# YOTSUBA_AP_EM_ver_4_0.net
KiCad netlist of a schematic drawn in EAGLE
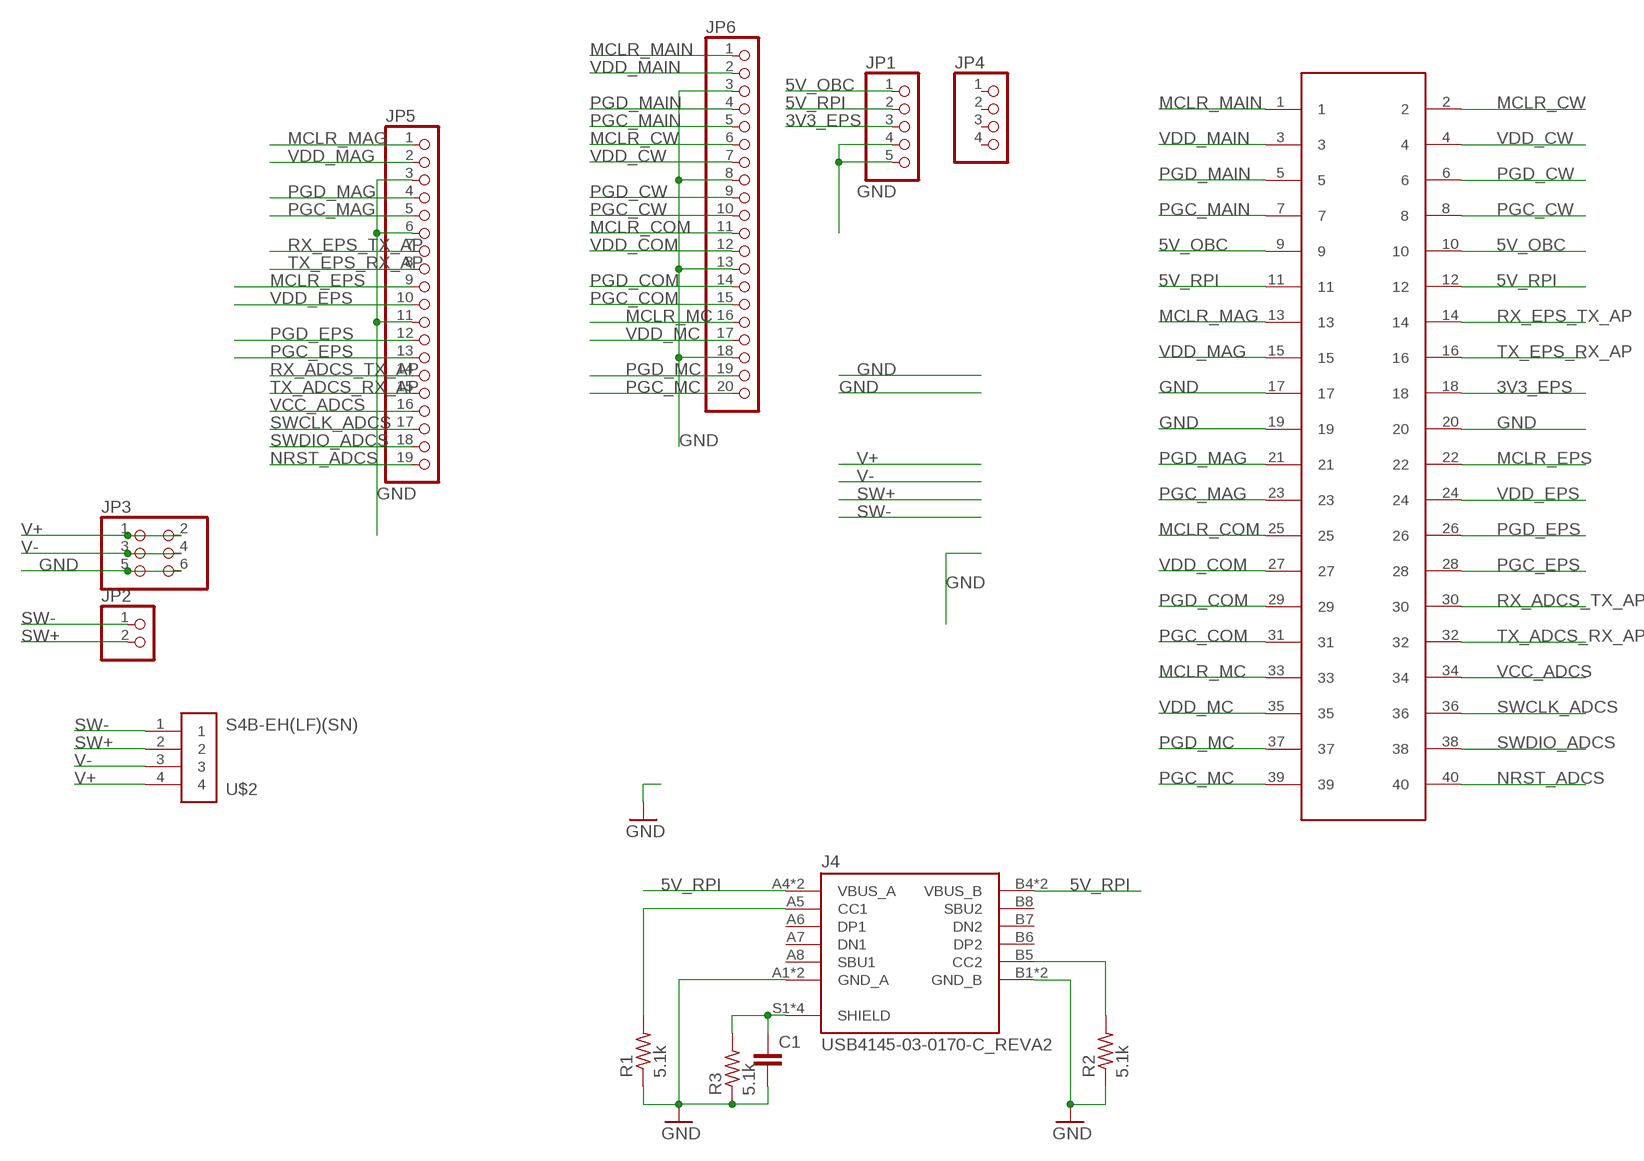
[diagram p0: schematic, sheet 1]

(export (version "E")
  (design (tool "Eeschema 10.0.6"))
  (components
    (comp (ref "C1")
      (value "C-EUC2012")
      (footprint "eagle-import:C2012")
      (libsource (lib "eagle-import") (part "C-EUC2012"))
    )
    (comp (ref "J4")
      (value "USB4145-03-0170-C_REVA2")
      (footprint "eagle-import:GCT_USB4145-03-0170-C_REVA2")
      (fields (field (name "MF") "Global Connector Technology") (field (name "MP") "USB4145-03-0170-C"))
      (libsource (lib "eagle-import") (part "USB4145-03-0170-C_REVA2"))
    )
    (comp (ref "JP1")
      (value "PINHD-1X5")
      (footprint "eagle-import:1X05")
      (libsource (lib "eagle-import") (part "PINHD-1X5"))
    )
    (comp (ref "JP2")
      (value "PINHD-1X2")
      (footprint "eagle-import:1X02")
      (libsource (lib "eagle-import") (part "PINHD-1X2"))
    )
    (comp (ref "JP3")
      (value "PINHD-2X3")
      (footprint "eagle-import:2X03")
      (libsource (lib "eagle-import") (part "PINHD-2X3"))
    )
    (comp (ref "JP4")
      (value "PINHD-1X4")
      (footprint "eagle-import:1X04")
      (libsource (lib "eagle-import") (part "PINHD-1X4"))
    )
    (comp (ref "JP5")
      (value "PINHD-1X19")
      (footprint "eagle-import:1X19")
      (libsource (lib "eagle-import") (part "PINHD-1X19"))
    )
    (comp (ref "JP6")
      (value "PINHD-1X20")
      (footprint "eagle-import:1X20")
      (libsource (lib "eagle-import") (part "PINHD-1X20"))
    )
    (comp (ref "R1")
      (value "5.1k")
      (footprint "eagle-import:R0805")
      (libsource (lib "eagle-import") (part "R-US_R0805"))
    )
    (comp (ref "R2")
      (value "5.1k")
      (footprint "eagle-import:R0805")
      (libsource (lib "eagle-import") (part "R-US_R0805"))
    )
    (comp (ref "R3")
      (value "5.1k")
      (footprint "eagle-import:R0805")
      (libsource (lib "eagle-import") (part "R-US_R0805"))
    )
    (comp (ref "U$1")
      (value "M50-3902042")
      (footprint "eagle-import:M50-3902042")
      (libsource (lib "eagle-import") (part "M50-3902042"))
    )
    (comp (ref "U$2")
      (value "S4B-EH(LF)(SN)")
      (footprint "eagle-import:JST_S4B-EH(LF)(SN)")
      (fields (field (name "MF") "JST Sales"))
      (libsource (lib "eagle-import") (part "S4B-EH(LF)(SN)"))
    )
  )
  (nets
    (net (code "1") (name "/3V3_EPS") (class "Default")
      (node (ref "JP1") (pin "3") (pinfunction "3_3") (pintype "passive"))
      (node (ref "U$1") (pin "18") (pinfunction "18_18") (pintype "bidirectional"))
    )
    (net (code "2") (name "/5V_OBC") (class "Default")
      (node (ref "JP1") (pin "1") (pinfunction "1_1") (pintype "passive"))
      (node (ref "U$1") (pin "10") (pinfunction "10_10") (pintype "bidirectional"))
      (node (ref "U$1") (pin "9") (pinfunction "9_9") (pintype "bidirectional"))
    )
    (net (code "3") (name "/5V_RPI") (class "Default")
      (node (ref "J4") (pin "A4") (pinfunction "VBUS_A_A4") (pintype "power_in"))
      (node (ref "J4") (pin "A9") (pinfunction "VBUS_A_A9") (pintype "power_in"))
      (node (ref "J4") (pin "B4") (pinfunction "VBUS_B_B4") (pintype "power_in"))
      (node (ref "J4") (pin "B9") (pinfunction "VBUS_B_B9") (pintype "power_in"))
      (node (ref "JP1") (pin "2") (pinfunction "2_2") (pintype "passive"))
      (node (ref "U$1") (pin "11") (pinfunction "11_11") (pintype "bidirectional"))
      (node (ref "U$1") (pin "12") (pinfunction "12_12") (pintype "bidirectional"))
    )
    (net (code "4") (name "/MCLR_COM") (class "Default")
      (node (ref "JP6") (pin "11") (pinfunction "11_11") (pintype "passive"))
      (node (ref "U$1") (pin "25") (pinfunction "25_25") (pintype "bidirectional"))
    )
    (net (code "5") (name "/MCLR_CW") (class "Default")
      (node (ref "JP6") (pin "6") (pinfunction "6_6") (pintype "passive"))
      (node (ref "U$1") (pin "2") (pinfunction "2_2") (pintype "bidirectional"))
    )
    (net (code "6") (name "/MCLR_EPS") (class "Default")
      (node (ref "JP5") (pin "9") (pinfunction "9_9") (pintype "passive"))
      (node (ref "U$1") (pin "22") (pinfunction "22_22") (pintype "bidirectional"))
    )
    (net (code "7") (name "/MCLR_MAG") (class "Default")
      (node (ref "JP5") (pin "1") (pinfunction "1_1") (pintype "passive"))
      (node (ref "U$1") (pin "13") (pinfunction "13_13") (pintype "bidirectional"))
    )
    (net (code "8") (name "/MCLR_MAIN") (class "Default")
      (node (ref "JP6") (pin "1") (pinfunction "1_1") (pintype "passive"))
      (node (ref "U$1") (pin "1") (pinfunction "1_1") (pintype "bidirectional"))
    )
    (net (code "9") (name "/MCLR_MC") (class "Default")
      (node (ref "JP6") (pin "16") (pinfunction "16_16") (pintype "passive"))
      (node (ref "U$1") (pin "33") (pinfunction "33_33") (pintype "bidirectional"))
    )
    (net (code "10") (name "/NRST_ADCS") (class "Default")
      (node (ref "JP5") (pin "19") (pinfunction "19_19") (pintype "passive"))
      (node (ref "U$1") (pin "40") (pinfunction "40_40") (pintype "bidirectional"))
    )
    (net (code "11") (name "/PGC_COM") (class "Default")
      (node (ref "JP6") (pin "15") (pinfunction "15_15") (pintype "passive"))
      (node (ref "U$1") (pin "31") (pinfunction "31_31") (pintype "bidirectional"))
    )
    (net (code "12") (name "/PGC_CW") (class "Default")
      (node (ref "JP6") (pin "10") (pinfunction "10_10") (pintype "passive"))
      (node (ref "U$1") (pin "8") (pinfunction "8_8") (pintype "bidirectional"))
    )
    (net (code "13") (name "/PGC_EPS") (class "Default")
      (node (ref "JP5") (pin "13") (pinfunction "13_13") (pintype "passive"))
      (node (ref "U$1") (pin "28") (pinfunction "28_28") (pintype "bidirectional"))
    )
    (net (code "14") (name "/PGC_MAG") (class "Default")
      (node (ref "JP5") (pin "5") (pinfunction "5_5") (pintype "passive"))
      (node (ref "U$1") (pin "23") (pinfunction "23_23") (pintype "bidirectional"))
    )
    (net (code "15") (name "/PGC_MAIN") (class "Default")
      (node (ref "JP6") (pin "5") (pinfunction "5_5") (pintype "passive"))
      (node (ref "U$1") (pin "7") (pinfunction "7_7") (pintype "bidirectional"))
    )
    (net (code "16") (name "/PGC_MC") (class "Default")
      (node (ref "JP6") (pin "20") (pinfunction "20_20") (pintype "passive"))
      (node (ref "U$1") (pin "39") (pinfunction "39_39") (pintype "bidirectional"))
    )
    (net (code "17") (name "/PGD_COM") (class "Default")
      (node (ref "JP6") (pin "14") (pinfunction "14_14") (pintype "passive"))
      (node (ref "U$1") (pin "29") (pinfunction "29_29") (pintype "bidirectional"))
    )
    (net (code "18") (name "/PGD_CW") (class "Default")
      (node (ref "JP6") (pin "9") (pinfunction "9_9") (pintype "passive"))
      (node (ref "U$1") (pin "6") (pinfunction "6_6") (pintype "bidirectional"))
    )
    (net (code "19") (name "/PGD_EPS") (class "Default")
      (node (ref "JP5") (pin "12") (pinfunction "12_12") (pintype "passive"))
      (node (ref "U$1") (pin "26") (pinfunction "26_26") (pintype "bidirectional"))
    )
    (net (code "20") (name "/PGD_MAG") (class "Default")
      (node (ref "JP5") (pin "4") (pinfunction "4_4") (pintype "passive"))
      (node (ref "U$1") (pin "21") (pinfunction "21_21") (pintype "bidirectional"))
    )
    (net (code "21") (name "/PGD_MAIN") (class "Default")
      (node (ref "JP6") (pin "4") (pinfunction "4_4") (pintype "passive"))
      (node (ref "U$1") (pin "5") (pinfunction "5_5") (pintype "bidirectional"))
    )
    (net (code "22") (name "/PGD_MC") (class "Default")
      (node (ref "JP6") (pin "19") (pinfunction "19_19") (pintype "passive"))
      (node (ref "U$1") (pin "37") (pinfunction "37_37") (pintype "bidirectional"))
    )
    (net (code "23") (name "/RX_ADCS_TX_AP") (class "Default")
      (node (ref "JP5") (pin "14") (pinfunction "14_14") (pintype "passive"))
      (node (ref "U$1") (pin "30") (pinfunction "30_30") (pintype "bidirectional"))
    )
    (net (code "24") (name "/RX_EPS_TX_AP") (class "Default")
      (node (ref "JP5") (pin "7") (pinfunction "7_7") (pintype "passive"))
      (node (ref "U$1") (pin "14") (pinfunction "14_14") (pintype "bidirectional"))
    )
    (net (code "25") (name "/SW+") (class "Default")
      (node (ref "JP2") (pin "2") (pinfunction "2_2") (pintype "passive"))
      (node (ref "U$2") (pin "2") (pinfunction "2_2") (pintype "passive"))
    )
    (net (code "26") (name "/SW-") (class "Default")
      (node (ref "JP2") (pin "1") (pinfunction "1_1") (pintype "passive"))
      (node (ref "U$2") (pin "1") (pinfunction "1_1") (pintype "passive"))
    )
    (net (code "27") (name "/SWCLK_ADCS") (class "Default")
      (node (ref "JP5") (pin "17") (pinfunction "17_17") (pintype "passive"))
      (node (ref "U$1") (pin "36") (pinfunction "36_36") (pintype "bidirectional"))
    )
    (net (code "28") (name "/SWDIO_ADCS") (class "Default")
      (node (ref "JP5") (pin "18") (pinfunction "18_18") (pintype "passive"))
      (node (ref "U$1") (pin "38") (pinfunction "38_38") (pintype "bidirectional"))
    )
    (net (code "29") (name "/TX_ADCS_RX_AP") (class "Default")
      (node (ref "JP5") (pin "15") (pinfunction "15_15") (pintype "passive"))
      (node (ref "U$1") (pin "32") (pinfunction "32_32") (pintype "bidirectional"))
    )
    (net (code "30") (name "/TX_EPS_RX_AP") (class "Default")
      (node (ref "JP5") (pin "8") (pinfunction "8_8") (pintype "passive"))
      (node (ref "U$1") (pin "16") (pinfunction "16_16") (pintype "bidirectional"))
    )
    (net (code "31") (name "/V+") (class "Default")
      (node (ref "JP3") (pin "1") (pinfunction "1_1") (pintype "passive"))
      (node (ref "JP3") (pin "2") (pinfunction "2_2") (pintype "passive"))
      (node (ref "U$2") (pin "4") (pinfunction "4_4") (pintype "passive"))
    )
    (net (code "32") (name "/V-") (class "Default")
      (node (ref "JP3") (pin "3") (pinfunction "3_3") (pintype "passive"))
      (node (ref "JP3") (pin "4") (pinfunction "4_4") (pintype "passive"))
      (node (ref "U$2") (pin "3") (pinfunction "3_3") (pintype "passive"))
    )
    (net (code "33") (name "/VCC_ADCS") (class "Default")
      (node (ref "JP5") (pin "16") (pinfunction "16_16") (pintype "passive"))
      (node (ref "U$1") (pin "34") (pinfunction "34_34") (pintype "bidirectional"))
    )
    (net (code "34") (name "/VDD_COM") (class "Default")
      (node (ref "JP6") (pin "12") (pinfunction "12_12") (pintype "passive"))
      (node (ref "U$1") (pin "27") (pinfunction "27_27") (pintype "bidirectional"))
    )
    (net (code "35") (name "/VDD_CW") (class "Default")
      (node (ref "JP6") (pin "7") (pinfunction "7_7") (pintype "passive"))
      (node (ref "U$1") (pin "4") (pinfunction "4_4") (pintype "bidirectional"))
    )
    (net (code "36") (name "/VDD_EPS") (class "Default")
      (node (ref "JP5") (pin "10") (pinfunction "10_10") (pintype "passive"))
      (node (ref "U$1") (pin "24") (pinfunction "24_24") (pintype "bidirectional"))
    )
    (net (code "37") (name "/VDD_MAG") (class "Default")
      (node (ref "JP5") (pin "2") (pinfunction "2_2") (pintype "passive"))
      (node (ref "U$1") (pin "15") (pinfunction "15_15") (pintype "bidirectional"))
    )
    (net (code "38") (name "/VDD_MAIN") (class "Default")
      (node (ref "JP6") (pin "2") (pinfunction "2_2") (pintype "passive"))
      (node (ref "U$1") (pin "3") (pinfunction "3_3") (pintype "bidirectional"))
    )
    (net (code "39") (name "/VDD_MC") (class "Default")
      (node (ref "JP6") (pin "17") (pinfunction "17_17") (pintype "passive"))
      (node (ref "U$1") (pin "35") (pinfunction "35_35") (pintype "bidirectional"))
    )
    (net (code "40") (name "GND") (class "Default")
      (node (ref "C1") (pin "2") (pinfunction "2_2") (pintype "passive"))
      (node (ref "J4") (pin "A1") (pinfunction "GND_A_A1") (pintype "power_in"))
      (node (ref "J4") (pin "A12") (pinfunction "GND_A_A12") (pintype "power_in"))
      (node (ref "J4") (pin "B1") (pinfunction "GND_B_B1") (pintype "power_in"))
      (node (ref "J4") (pin "B12") (pinfunction "GND_B_B12") (pintype "power_in"))
      (node (ref "JP1") (pin "4") (pinfunction "4_4") (pintype "passive"))
      (node (ref "JP1") (pin "5") (pinfunction "5_5") (pintype "passive"))
      (node (ref "JP3") (pin "5") (pinfunction "5_5") (pintype "passive"))
      (node (ref "JP3") (pin "6") (pinfunction "6_6") (pintype "passive"))
      (node (ref "JP5") (pin "11") (pinfunction "11_11") (pintype "passive"))
      (node (ref "JP5") (pin "3") (pinfunction "3_3") (pintype "passive"))
      (node (ref "JP5") (pin "6") (pinfunction "6_6") (pintype "passive"))
      (node (ref "JP6") (pin "13") (pinfunction "13_13") (pintype "passive"))
      (node (ref "JP6") (pin "18") (pinfunction "18_18") (pintype "passive"))
      (node (ref "JP6") (pin "3") (pinfunction "3_3") (pintype "passive"))
      (node (ref "JP6") (pin "8") (pinfunction "8_8") (pintype "passive"))
      (node (ref "R1") (pin "1") (pinfunction "1_1") (pintype "passive"))
      (node (ref "R2") (pin "1") (pinfunction "1_1") (pintype "passive"))
      (node (ref "R3") (pin "1") (pinfunction "1_1") (pintype "passive"))
      (node (ref "U$1") (pin "17") (pinfunction "17_17") (pintype "bidirectional"))
      (node (ref "U$1") (pin "19") (pinfunction "19_19") (pintype "bidirectional"))
      (node (ref "U$1") (pin "20") (pinfunction "20_20") (pintype "bidirectional"))
    )
    (net (code "41") (name "Net-(C1-Pad1)") (class "Default")
      (node (ref "C1") (pin "1") (pinfunction "1_1") (pintype "passive"))
      (node (ref "J4") (pin "S1") (pinfunction "SHIELD_S1") (pintype "passive"))
      (node (ref "J4") (pin "S2") (pinfunction "SHIELD_S2") (pintype "passive"))
      (node (ref "J4") (pin "S3") (pinfunction "SHIELD_S3") (pintype "passive"))
      (node (ref "J4") (pin "S4") (pinfunction "SHIELD_S4") (pintype "passive"))
      (node (ref "R3") (pin "2") (pinfunction "2_2") (pintype "passive"))
    )
    (net (code "42") (name "Net-(J4-CC1)") (class "Default")
      (node (ref "J4") (pin "A5") (pinfunction "CC1_A5") (pintype "bidirectional"))
      (node (ref "R1") (pin "2") (pinfunction "2_2") (pintype "passive"))
    )
    (net (code "43") (name "Net-(J4-CC2)") (class "Default")
      (node (ref "J4") (pin "B5") (pinfunction "CC2_B5") (pintype "bidirectional"))
      (node (ref "R2") (pin "2") (pinfunction "2_2") (pintype "passive"))
    )
    (net (code "44") (name "unconnected-(J4-DN1-PadA7)") (class "Default")
      (node (ref "J4") (pin "A7") (pinfunction "DN1_A7") (pintype "bidirectional"))
    )
    (net (code "45") (name "unconnected-(J4-DN2-PadB7)") (class "Default")
      (node (ref "J4") (pin "B7") (pinfunction "DN2_B7") (pintype "bidirectional"))
    )
    (net (code "46") (name "unconnected-(J4-DP1-PadA6)") (class "Default")
      (node (ref "J4") (pin "A6") (pinfunction "DP1_A6") (pintype "bidirectional"))
    )
    (net (code "47") (name "unconnected-(J4-DP2-PadB6)") (class "Default")
      (node (ref "J4") (pin "B6") (pinfunction "DP2_B6") (pintype "bidirectional"))
    )
    (net (code "48") (name "unconnected-(J4-SBU1-PadA8)") (class "Default")
      (node (ref "J4") (pin "A8") (pinfunction "SBU1_A8") (pintype "bidirectional"))
    )
    (net (code "49") (name "unconnected-(J4-SBU2-PadB8)") (class "Default")
      (node (ref "J4") (pin "B8") (pinfunction "SBU2_B8") (pintype "bidirectional"))
    )
    (net (code "50") (name "unconnected-(JP4-Pad1)") (class "Default")
      (node (ref "JP4") (pin "1") (pinfunction "1_1") (pintype "passive"))
    )
    (net (code "51") (name "unconnected-(JP4-Pad2)") (class "Default")
      (node (ref "JP4") (pin "2") (pinfunction "2_2") (pintype "passive"))
    )
    (net (code "52") (name "unconnected-(JP4-Pad3)") (class "Default")
      (node (ref "JP4") (pin "3") (pinfunction "3_3") (pintype "passive"))
    )
    (net (code "53") (name "unconnected-(JP4-Pad4)") (class "Default")
      (node (ref "JP4") (pin "4") (pinfunction "4_4") (pintype "passive"))
    )
  )
)
